# Enable_SSR.net
KiCad netlist of a schematic drawn in Altium Designer
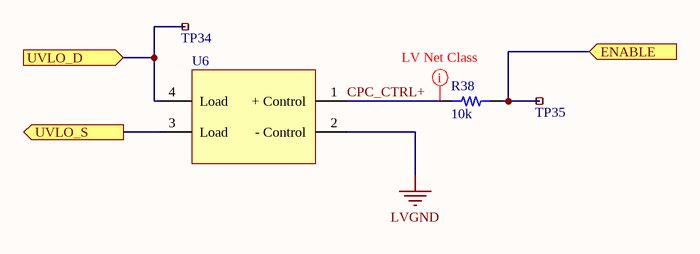
[diagram p0: Enable SSR.SchDoc]

(export (version "E")
  (design (tool "Eeschema 10.0.6"))
  (components
    (comp (ref "R38")
      (value "10k")
      (footprint "RES 0603/1608")
      (fields
        (field (name "TOLERANCE") "1%")
        (field (name "POWER") "1/10W")
        (field (name "Comment") "Resistor 10k 0603 1/10W 1%")
        (field (name "CREATED_BY") "Nick Mah")
      )
      (libsource (lib "Altium-Lib") (part "Resistor"))
    )
    (comp (ref "TP34")
      (value "RCU-0C")
      (footprint "5029")
      (description "Test point")
      (fields
        (field (name "MFRPARTNO") "5029")
        (field (name "COMPONENTLINK1URL") "file:///C:/Users/Jason%20Zhou/Downloads/5029.PDF")
        (field (name "CREATED_BY") "Jason Zhou")
      )
      (libsource (lib "Altium-Lib") (part "RCU-0C"))
    )
    (comp (ref "TP35")
      (value "RCU-0C")
      (footprint "5029")
      (description "Test point")
      (fields
        (field (name "MFRPARTNO") "5029")
        (field (name "COMPONENTLINK1URL") "file:///C:/Users/Jason%20Zhou/Downloads/5029.PDF")
        (field (name "CREATED_BY") "Jason Zhou")
      )
      (libsource (lib "Altium-Lib") (part "RCU-0C"))
    )
    (comp (ref "U6")
      (value "~")
      (footprint "CPC1393GR")
      (description "Solid State Relay SPST-NO (1 Form A) 4-SMD (0.300\", 7.62mm)")
      (fields
        (field (name "MFRPARTNO") "CPC1393GRTR")
        (field (name "CREATED_BY") "Lynette")
        (field (name "UPDATED_BY") "Null")
      )
      (libsource (lib "Altium-Lib") (part "CPC1393"))
    )
  )
  (nets
    (net (code "1") (name "/CPC_CTRL+") (class "Default")
      (node (ref "R38") (pin "1") (pinfunction "1_1") (pintype "passive"))
      (node (ref "U6") (pin "1") (pinfunction "+_Control_1") (pintype "passive"))
    )
    (net (code "2") (name "/ENABLE") (class "Default")
      (node (ref "R38") (pin "2") (pinfunction "2_2") (pintype "passive"))
      (node (ref "TP35") (pin "1") (pintype "passive"))
    )
    (net (code "3") (name "/UVLO_D") (class "Default")
      (node (ref "TP34") (pin "1") (pintype "passive"))
      (node (ref "U6") (pin "4") (pinfunction "Load_4") (pintype "passive"))
    )
    (net (code "4") (name "/UVLO_S") (class "Default")
      (node (ref "U6") (pin "3") (pinfunction "Load_3") (pintype "passive"))
    )
    (net (code "5") (name "LVGND") (class "Default")
      (node (ref "U6") (pin "2") (pinfunction "-_Control_2") (pintype "passive"))
    )
  )
)
